# Block_Diagram.net
KiCad netlist of a schematic drawn in Altium Designer
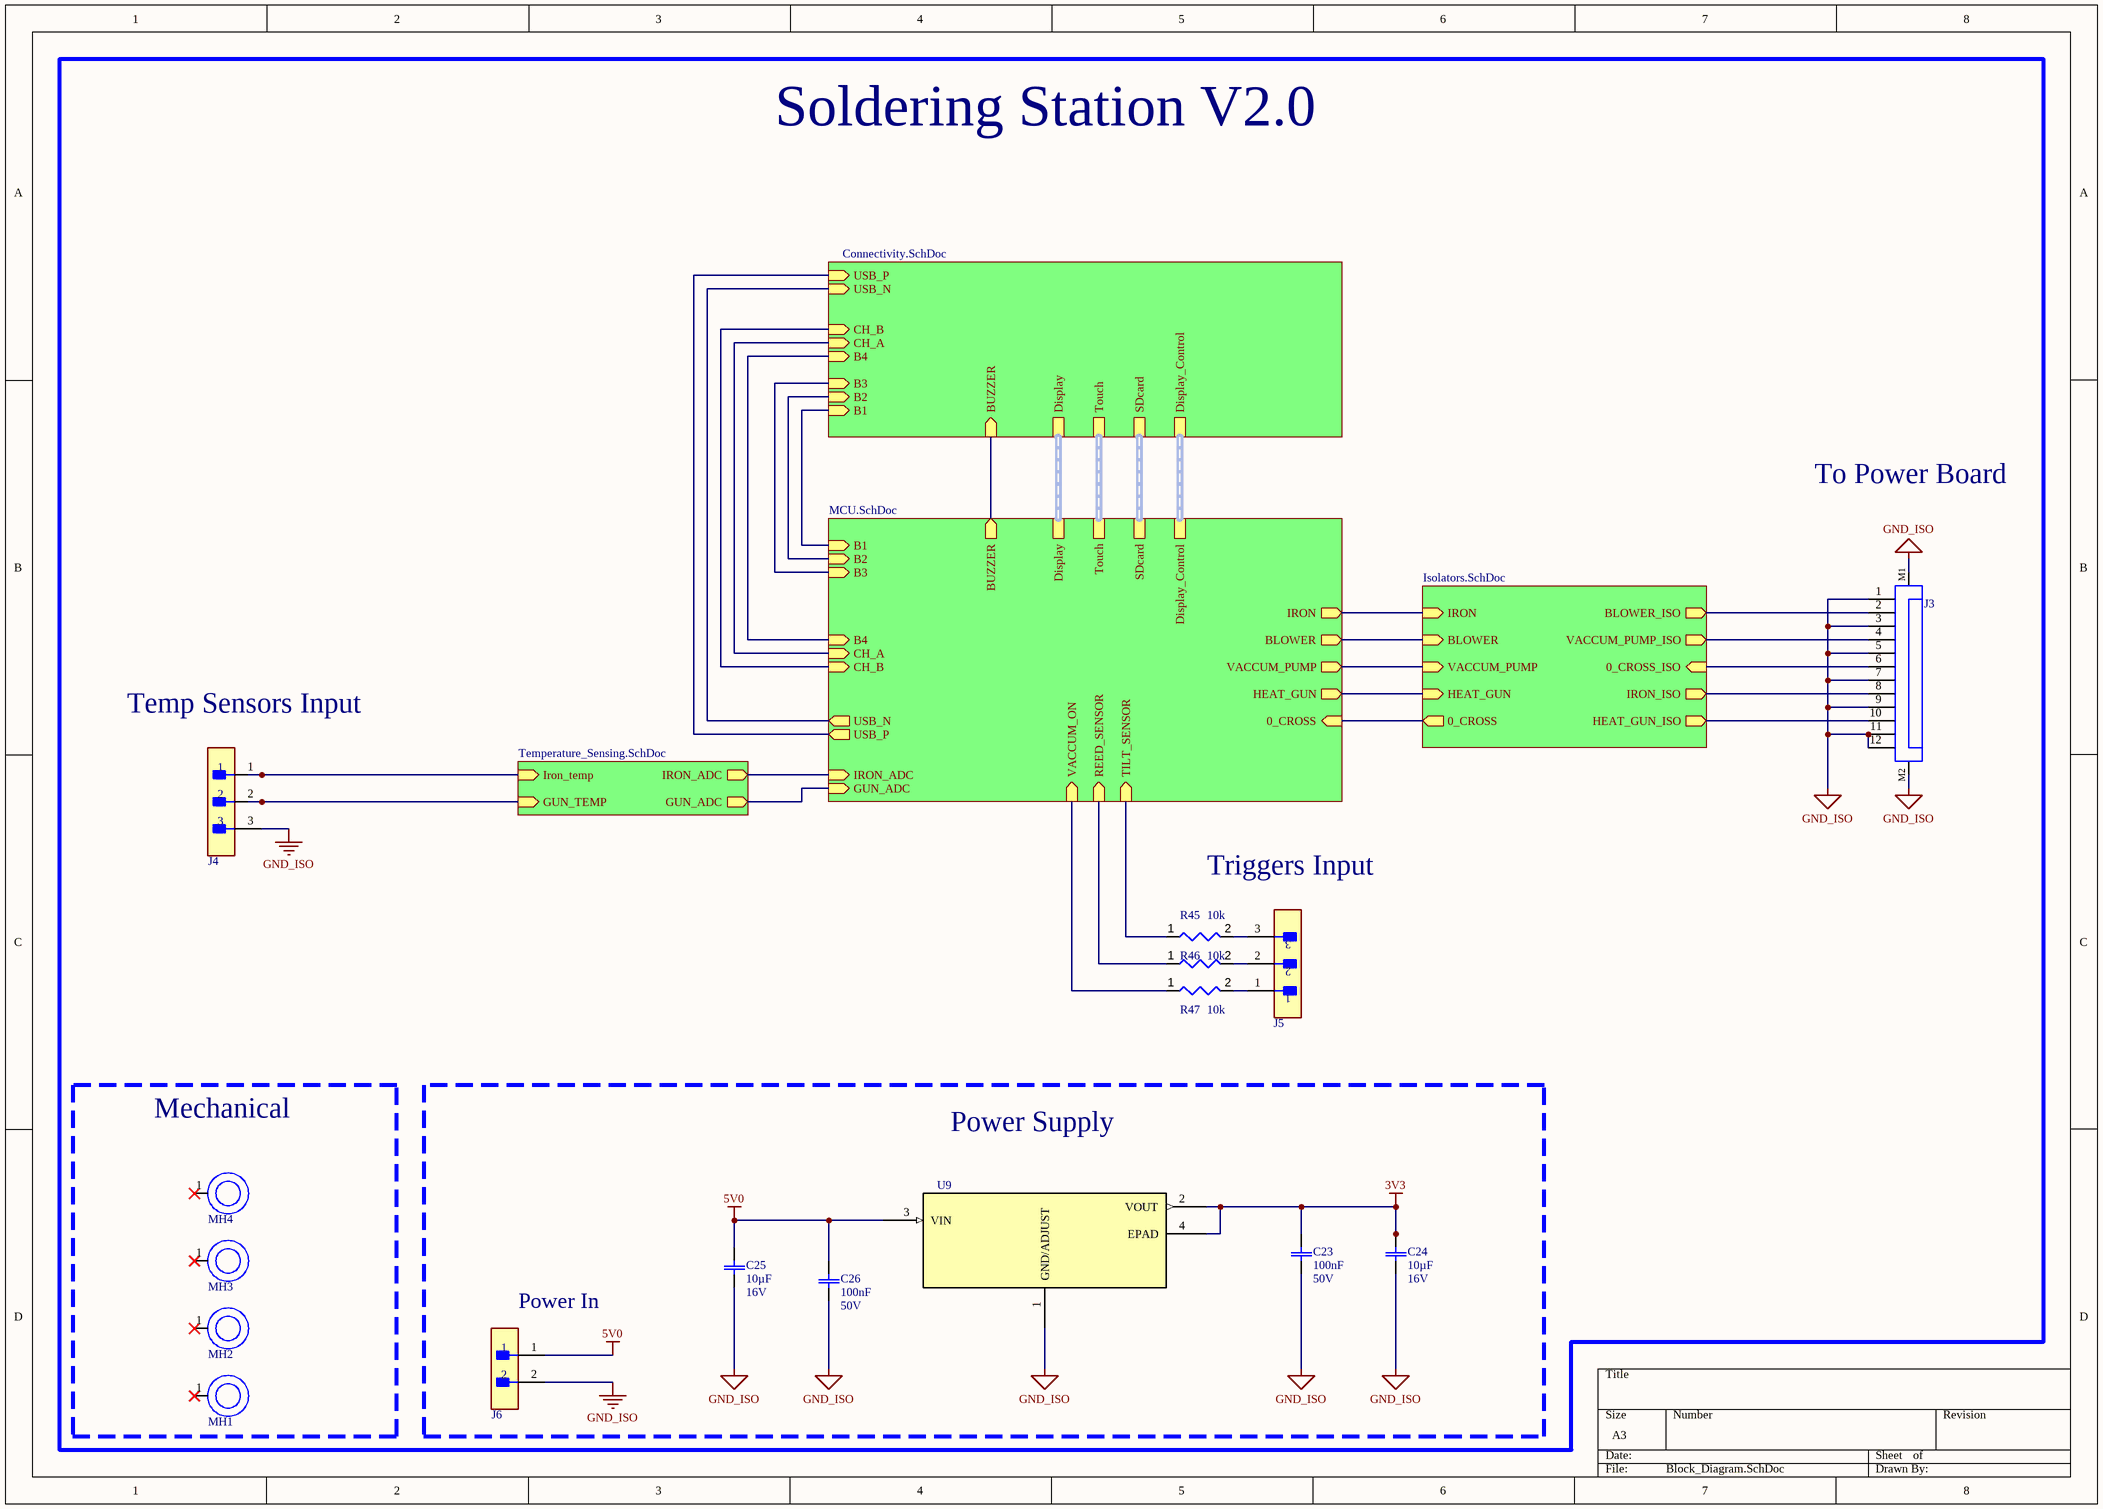
[diagram p0: Block_Diagram.SchDoc]

(export (version "E")
  (design (tool "Eeschema 10.0.6"))
  (components
    (comp (ref "C23")
      (value "100nF")
      (footprint "Generic Ceramic 0603 CAP")
      (fields
        (field (name "VOLTAGE RATING") "50V")
        (field (name "Comment") "CAP-MLCC_SMD-0603_MR-GCM_u_0.1uF_50V_10%_X8L")
      )
      (libsource (lib "Paulo Peixoto") (part "CAP_Ceramic"))
    )
    (comp (ref "C24")
      (value "10µF")
      (footprint "Generic Ceramic 0805 CAP")
      (fields
        (field (name "VOLTAGE RATING") "16V")
        (field (name "TOLERANCE") "20%")
        (field (name "Comment") "CAP-MLCC_SMD-0805_TDK-CGA_u_10uF_16V_20%_X7S")
      )
      (libsource (lib "Paulo Peixoto") (part "CAP_Ceramic"))
    )
    (comp (ref "C25")
      (value "10µF")
      (footprint "Generic Ceramic 0805 CAP")
      (fields
        (field (name "VOLTAGE RATING") "16V")
        (field (name "TOLERANCE") "20%")
        (field (name "Comment") "CAP-MLCC_SMD-0805_TDK-CGA_u_10uF_16V_20%_X7S")
      )
      (libsource (lib "Paulo Peixoto") (part "CAP_Ceramic"))
    )
    (comp (ref "C26")
      (value "100nF")
      (footprint "Generic Ceramic 0603 CAP")
      (fields
        (field (name "VOLTAGE RATING") "50V")
        (field (name "Comment") "CAP-MLCC_SMD-0603_MR-GCM_u_0.1uF_50V_10%_X8L")
      )
      (libsource (lib "Paulo Peixoto") (part "CAP_Ceramic"))
    )
    (comp (ref "J3")
      (value "687112183622")
      (footprint "687112183622")
      (libsource (lib "Altium Content Vault") (part "FPC - 12P - 2MP"))
    )
    (comp (ref "J4")
      (value "B3P-SHF-1AA(LF)(SN)")
      (footprint "FP-B3P-SHF-1AA_LF_SN-MFG")
      (description "CONN HEADER VERT 3POS 2.5MM")
      (libsource (lib "Altium Content Vault") (part "0d3f023dd272f625e17a2be33dea85f"))
    )
    (comp (ref "J5")
      (value "B3P-SHF-1AA(LF)(SN)")
      (footprint "FP-B3P-SHF-1AA_LF_SN-MFG")
      (description "CONN HEADER VERT 3POS 2.5MM")
      (libsource (lib "") (part "0d3f023dd272f625e17a2be33dea85f_1"))
    )
    (comp (ref "J6")
      (value "B2B-XH-A(LF)(SN)")
      (footprint "FP-B2B-XH-A_LF_SN-MFG")
      (description "CONNECTOR HEADER, XH SERIES, 2 POSITION, 2.50MM, Press-Fit Solder, Detent Lock, Natural")
      (libsource (lib "Paulo Peixoto") (part "3bc925449376181038e59eaffc5286c"))
    )
    (comp (ref "MH1")
      (value "3mm_Mounting_Hole")
      (footprint "Single_3mm_Mounting_Hole")
      (description "3.2mm, sPad Mounting Hole")
      (libsource (lib "Paulo Peixoto") (part "Generic_Mounting_Hole"))
    )
    (comp (ref "MH2")
      (value "3mm_Mounting_Hole")
      (footprint "Single_3mm_Mounting_Hole")
      (description "3.2mm, sPad Mounting Hole")
      (libsource (lib "Paulo Peixoto") (part "Generic_Mounting_Hole"))
    )
    (comp (ref "MH3")
      (value "3mm_Mounting_Hole")
      (footprint "Single_3mm_Mounting_Hole")
      (description "3.2mm, sPad Mounting Hole")
      (libsource (lib "Paulo Peixoto") (part "Generic_Mounting_Hole"))
    )
    (comp (ref "MH4")
      (value "3mm_Mounting_Hole")
      (footprint "Single_3mm_Mounting_Hole")
      (description "3.2mm, sPad Mounting Hole")
      (libsource (lib "Paulo Peixoto") (part "Generic_Mounting_Hole"))
    )
    (comp (ref "R45")
      (value "10k")
      (footprint "Generic_0603_RES")
      (fields
        (field (name "TOLERANCE") "1%")
        (field (name "POWER") "100mW")
        (field (name "Comment") "RES-TK_SMD-0603_VIS-CRCW_K_10K_1/10W_1%")
      )
      (libsource (lib "Paulo Peixoto") (part "Res"))
    )
    (comp (ref "R46")
      (value "10k")
      (footprint "Generic_0603_RES")
      (fields
        (field (name "TOLERANCE") "1%")
        (field (name "POWER") "100mW")
        (field (name "Comment") "RES-TK_SMD-0603_VIS-CRCW_K_10K_1/10W_1%")
      )
      (libsource (lib "Paulo Peixoto") (part "Res"))
    )
    (comp (ref "R47")
      (value "10k")
      (footprint "Generic_0603_RES")
      (fields
        (field (name "TOLERANCE") "1%")
        (field (name "POWER") "100mW")
        (field (name "Comment") "RES-TK_SMD-0603_VIS-CRCW_K_10K_1/10W_1%")
      )
      (libsource (lib "Paulo Peixoto") (part "Res"))
    )
    (comp (ref "U9")
      (value "AMS1117-3.3")
      (footprint "AMS1117-3.3-Footprint-1")
      (libsource (lib "Paulo Peixoto") (part "AMS1117-3.3-Symbol-1"))
    )
  )
  (nets
    (net (code "2") (name "/0_CROSS_ISO") (class "Default")
      (node (ref "J3") (pin "6") (pinfunction "6_6") (pintype "passive"))
    )
    (net (code "8") (name "/BLOWER_ISO") (class "Default")
      (node (ref "J3") (pin "2") (pinfunction "2_2") (pintype "passive"))
    )
    (net (code "15") (name "/GUN_TEMP") (class "Default")
      (node (ref "J4") (pin "2") (pinfunction "2_2") (pintype "passive"))
    )
    (net (code "17") (name "/HEAT_GUN_ISO") (class "Default")
      (node (ref "J3") (pin "10") (pinfunction "10_10") (pintype "passive"))
    )
    (net (code "20") (name "/IRON_ISO") (class "Default")
      (node (ref "J3") (pin "8") (pinfunction "8_8") (pintype "passive"))
    )
    (net (code "21") (name "/Iron_temp") (class "Default")
      (node (ref "J4") (pin "1") (pinfunction "1_1") (pintype "passive"))
    )
    (net (code "22") (name "/REED_SENSOR") (class "Default")
      (node (ref "R46") (pin "1") (pinfunction "1_1") (pintype "passive"))
    )
    (net (code "24") (name "/TILT_SENSOR") (class "Default")
      (node (ref "R45") (pin "1") (pinfunction "1_1") (pintype "passive"))
    )
    (net (code "28") (name "/VACCUM_ON") (class "Default")
      (node (ref "R47") (pin "1") (pinfunction "1_1") (pintype "passive"))
    )
    (net (code "30") (name "/VACCUM_PUMP_ISO") (class "Default")
      (node (ref "J3") (pin "4") (pinfunction "4_4") (pintype "passive"))
    )
    (net (code "31") (name "3V3") (class "Default")
      (node (ref "C23") (pin "2") (pinfunction "2_2") (pintype "passive"))
      (node (ref "C24") (pin "2") (pinfunction "2_2") (pintype "passive"))
      (node (ref "U9") (pin "2") (pinfunction "VOUT_2") (pintype "output"))
      (node (ref "U9") (pin "4") (pinfunction "EPAD_4") (pintype "power_in"))
    )
    (net (code "32") (name "5V0") (class "Default")
      (node (ref "C25") (pin "2") (pinfunction "2_2") (pintype "passive"))
      (node (ref "C26") (pin "2") (pinfunction "2_2") (pintype "passive"))
      (node (ref "J6") (pin "1") (pinfunction "1_1") (pintype "passive"))
      (node (ref "U9") (pin "3") (pinfunction "VIN_3") (pintype "input"))
    )
    (net (code "33") (name "GND_ISO") (class "Default")
      (node (ref "C23") (pin "1") (pinfunction "1_1") (pintype "passive"))
      (node (ref "C24") (pin "1") (pinfunction "1_1") (pintype "passive"))
      (node (ref "C25") (pin "1") (pinfunction "1_1") (pintype "passive"))
      (node (ref "C26") (pin "1") (pinfunction "1_1") (pintype "passive"))
      (node (ref "J3") (pin "1") (pinfunction "1_1") (pintype "passive"))
      (node (ref "J3") (pin "11") (pinfunction "11_11") (pintype "passive"))
      (node (ref "J3") (pin "12") (pinfunction "12_12") (pintype "passive"))
      (node (ref "J3") (pin "3") (pinfunction "3_3") (pintype "passive"))
      (node (ref "J3") (pin "5") (pinfunction "5_5") (pintype "passive"))
      (node (ref "J3") (pin "7") (pinfunction "7_7") (pintype "passive"))
      (node (ref "J3") (pin "9") (pinfunction "9_9") (pintype "passive"))
      (node (ref "J3") (pin "M1") (pinfunction "M1_M1") (pintype "passive"))
      (node (ref "J3") (pin "M2") (pinfunction "M2_M2") (pintype "passive"))
      (node (ref "J4") (pin "3") (pinfunction "3_3") (pintype "passive"))
      (node (ref "J6") (pin "2") (pinfunction "2_2") (pintype "passive"))
      (node (ref "U9") (pin "1") (pinfunction "GND/ADJUST_1") (pintype "power_in"))
    )
    (net (code "34") (name "Net-(J5-Pad1)") (class "Default")
      (node (ref "J5") (pin "1") (pinfunction "1_1") (pintype "passive"))
      (node (ref "R47") (pin "2") (pinfunction "2_2") (pintype "passive"))
    )
    (net (code "35") (name "Net-(J5-Pad2)") (class "Default")
      (node (ref "J5") (pin "2") (pinfunction "2_2") (pintype "passive"))
      (node (ref "R46") (pin "2") (pinfunction "2_2") (pintype "passive"))
    )
    (net (code "36") (name "Net-(J5-Pad3)") (class "Default")
      (node (ref "J5") (pin "3") (pinfunction "3_3") (pintype "passive"))
      (node (ref "R45") (pin "2") (pinfunction "2_2") (pintype "passive"))
    )
    (net (code "37") (name "unconnected-(MH1-Pad1)") (class "Default")
      (node (ref "MH1") (pin "1") (pinfunction "1_1") (pintype "passive+no_connect"))
    )
    (net (code "38") (name "unconnected-(MH2-Pad1)") (class "Default")
      (node (ref "MH2") (pin "1") (pinfunction "1_1") (pintype "passive+no_connect"))
    )
    (net (code "39") (name "unconnected-(MH3-Pad1)") (class "Default")
      (node (ref "MH3") (pin "1") (pinfunction "1_1") (pintype "passive+no_connect"))
    )
    (net (code "40") (name "unconnected-(MH4-Pad1)") (class "Default")
      (node (ref "MH4") (pin "1") (pinfunction "1_1") (pintype "passive+no_connect"))
    )
  )
)
